# Schematic_EBook_v24.net
KiCad netlist of a schematic drawn in EAGLE
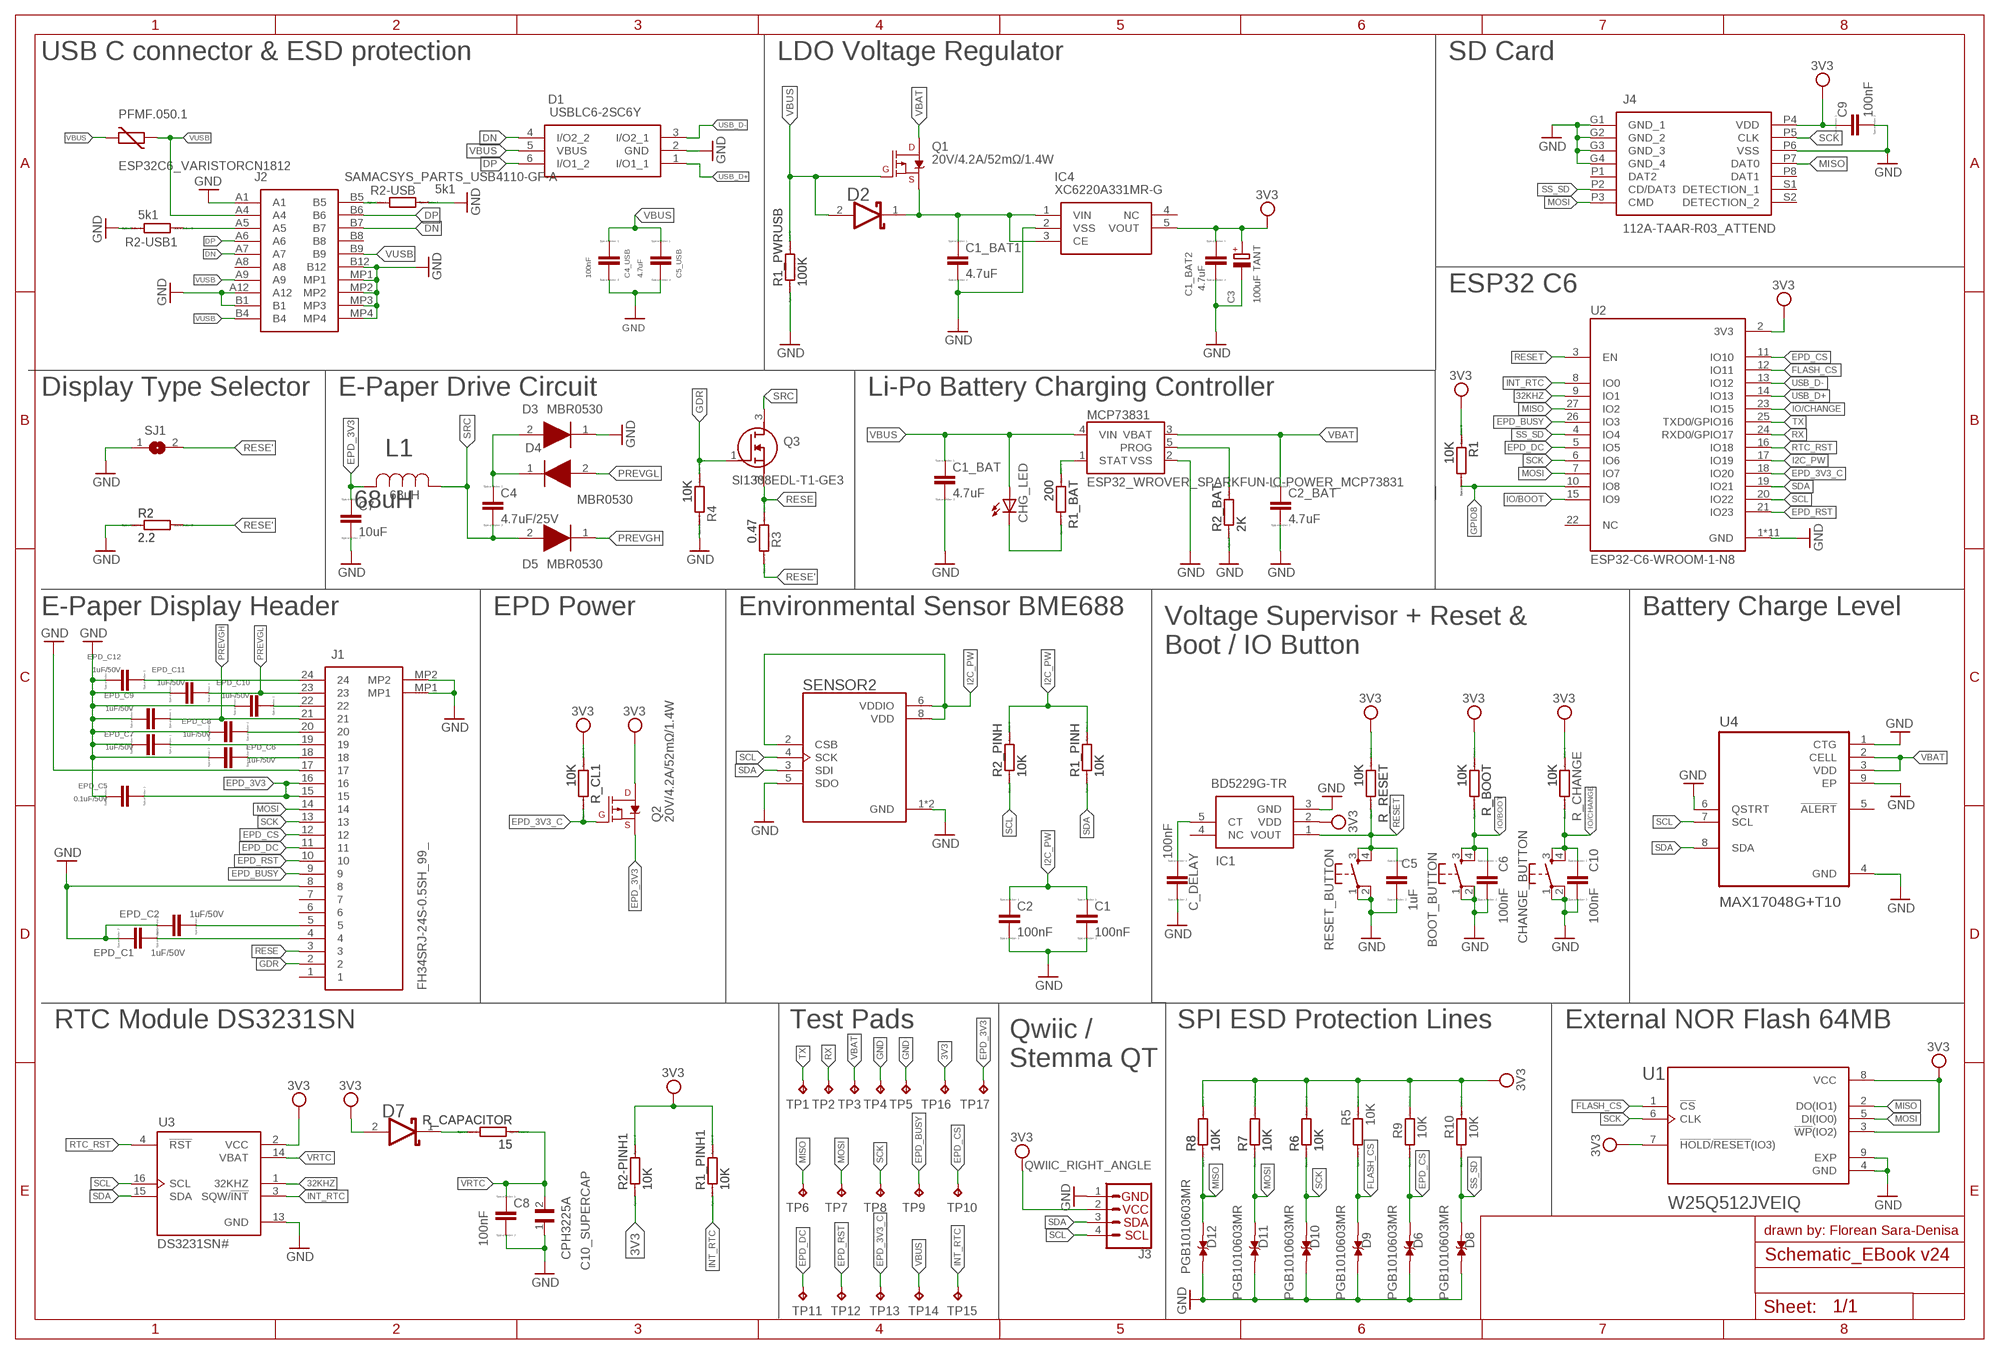
[diagram p0: schematic, sheet 1]

(export (version "E")
  (design (tool "Eeschema 10.0.6"))
  (components
    (comp (ref "BOOT_BUTTON")
      (value "BUTTON_CUSYOMV1")
      (footprint "eagle-import:MYBUTTON")
      (libsource (lib "eagle-import") (part "BUTTON_CUSYOMV1"))
    )
    (comp (ref "C1")
      (value "100nF")
      (footprint "eagle-import:EAGLE-LTSPICE_C0402")
      (libsource (lib "eagle-import") (part "EAGLE-LTSPICE_CC0402"))
    )
    (comp (ref "C1_BAT")
      (value "4.7uF")
      (footprint "eagle-import:EAGLE-LTSPICE_C0402")
      (libsource (lib "eagle-import") (part "EAGLE-LTSPICE_CC0402"))
    )
    (comp (ref "C1_BAT1")
      (value "4.7uF")
      (footprint "eagle-import:EAGLE-LTSPICE_C0402")
      (libsource (lib "eagle-import") (part "EAGLE-LTSPICE_CC0402"))
    )
    (comp (ref "C1_BAT2")
      (value "4.7uF")
      (footprint "eagle-import:EAGLE-LTSPICE_C0402")
      (libsource (lib "eagle-import") (part "ESP32_WROVER_EAGLE-LTSPICE_CC0402"))
    )
    (comp (ref "C2")
      (value "100nF")
      (footprint "eagle-import:EAGLE-LTSPICE_C0402")
      (libsource (lib "eagle-import") (part "EAGLE-LTSPICE_CC0402"))
    )
    (comp (ref "C2_BAT")
      (value "4.7uF")
      (footprint "eagle-import:EAGLE-LTSPICE_C0402")
      (libsource (lib "eagle-import") (part "EAGLE-LTSPICE_CC0402"))
    )
    (comp (ref "C3")
      (value "100uF TANT")
      (footprint "eagle-import:RCL_CT3528")
      (libsource (lib "eagle-import") (part "RCL_CPOL-EUCT3528"))
    )
    (comp (ref "C4")
      (value "4.7uF/25V")
      (footprint "eagle-import:EAGLE-LTSPICE_C0402")
      (libsource (lib "eagle-import") (part "EAGLE-LTSPICE_CC0402"))
    )
    (comp (ref "C4_USB")
      (value "100nF")
      (footprint "eagle-import:EAGLE-LTSPICE_C0402")
      (libsource (lib "eagle-import") (part "EAGLE-LTSPICE_CC0402"))
    )
    (comp (ref "C5")
      (value "1uF")
      (footprint "eagle-import:EAGLE-LTSPICE_C0402")
      (libsource (lib "eagle-import") (part "EAGLE-LTSPICE_CC0402"))
    )
    (comp (ref "C5_USB")
      (value "4.7uF")
      (footprint "eagle-import:EAGLE-LTSPICE_C0402")
      (libsource (lib "eagle-import") (part "EAGLE-LTSPICE_CC0402"))
    )
    (comp (ref "C6")
      (value "100nF")
      (footprint "eagle-import:EAGLE-LTSPICE_C0402")
      (libsource (lib "eagle-import") (part "EAGLE-LTSPICE_CC0402"))
    )
    (comp (ref "C7")
      (value "10uF")
      (footprint "eagle-import:EAGLE-LTSPICE_C0402")
      (libsource (lib "eagle-import") (part "EAGLE-LTSPICE_CC0402"))
    )
    (comp (ref "C8")
      (value "100nF")
      (footprint "eagle-import:EAGLE-LTSPICE_C0402")
      (libsource (lib "eagle-import") (part "EAGLE-LTSPICE_CC0402"))
    )
    (comp (ref "C9")
      (value "100nF")
      (footprint "eagle-import:EAGLE-LTSPICE_C0402")
      (libsource (lib "eagle-import") (part "EAGLE-LTSPICE_CC0402"))
    )
    (comp (ref "C10")
      (value "100nF")
      (footprint "eagle-import:EAGLE-LTSPICE_C0402")
      (libsource (lib "eagle-import") (part "EAGLE-LTSPICE_CC0402"))
    )
    (comp (ref "C10_SUPERCAP")
      (value "CPH3225A")
      (footprint "eagle-import:CAPCP3225X100N")
      (fields (field (name "MF") "Seiko Instruments"))
      (libsource (lib "eagle-import") (part "CPH3225A"))
    )
    (comp (ref "CHANGE_BUTTON")
      (value "BUTTON_CUSYOMV1")
      (footprint "eagle-import:MYBUTTON")
      (libsource (lib "eagle-import") (part "BUTTON_CUSYOMV1"))
    )
    (comp (ref "CHG_LED")
      (value "&")
      (footprint "eagle-import:ADAFRUIT_CHIP-LED0603")
      (libsource (lib "eagle-import") (part "ADAFRUIT_LEDCHIP-LED0603"))
    )
    (comp (ref "C_DELAY")
      (value "100nF")
      (footprint "eagle-import:EAGLE-LTSPICE_C0402")
      (libsource (lib "eagle-import") (part "EAGLE-LTSPICE_CC0402"))
    )
    (comp (ref "D1")
      (value "USBLC6-2SC6Y")
      (footprint "eagle-import:SOT95P280X145-6N")
      (fields (field (name "MF") "STMicroelectronics"))
      (libsource (lib "eagle-import") (part "USBLC6-2SC6Y"))
    )
    (comp (ref "D2")
      (value "ESP32_WROVER_AVX---SD0805S020S1R0_AVX_SD0805S020S1R0_0_0AVX_SD0805S020S1R0_0_0")
      (footprint "eagle-import:ESP32_WROVER_AVX---SD0805S020S1R0_AVX_SD0805S020S1R0_0")
      (fields
        (field (name "DIGIKEY_PART_NUMBER") "478-7800-1-ND")
        (field (name "MF") "AVX")
        (field (name "MOUSER_PART_NUMBER") "581-SD0805S020S1R0")
      )
      (libsource (lib "eagle-import") (part "ESP32_WROVER_AVX---SD0805S020S1R0_AVX_SD0805S020S1R0_0_0AVX_SD0805S020S1R0_0_0"))
    )
    (comp (ref "D3")
      (value "MBR0530")
      (footprint "eagle-import:SOD3716X135N")
      (fields (field (name "MF") "ON Semiconductor"))
      (libsource (lib "eagle-import") (part "MBR0530"))
    )
    (comp (ref "D4")
      (value "MBR0530")
      (footprint "eagle-import:SOD3716X135N")
      (fields (field (name "MF") "ON Semiconductor"))
      (libsource (lib "eagle-import") (part "MBR0530"))
    )
    (comp (ref "D5")
      (value "MBR0530")
      (footprint "eagle-import:SOD3716X135N")
      (fields (field (name "MF") "ON Semiconductor"))
      (libsource (lib "eagle-import") (part "MBR0530"))
    )
    (comp (ref "D6")
      (value "PGB1010603MR")
      (footprint "eagle-import:DIOC1608X36N")
      (fields (field (name "MF") "Littelfuse Inc."))
      (libsource (lib "eagle-import") (part "PGB1010603MR"))
    )
    (comp (ref "D7")
      (value "ESP32_WROVER_AVX---SD0805S020S1R0_AVX_SD0805S020S1R0_0_0AVX_SD0805S020S1R0_0_0")
      (footprint "eagle-import:ESP32_WROVER_AVX---SD0805S020S1R0_AVX_SD0805S020S1R0_0")
      (fields
        (field (name "DIGIKEY_PART_NUMBER") "478-7800-1-ND")
        (field (name "MF") "AVX")
        (field (name "MOUSER_PART_NUMBER") "581-SD0805S020S1R0")
      )
      (libsource (lib "eagle-import") (part "ESP32_WROVER_AVX---SD0805S020S1R0_AVX_SD0805S020S1R0_0_0AVX_SD0805S020S1R0_0_0"))
    )
    (comp (ref "D8")
      (value "PGB1010603MR")
      (footprint "eagle-import:DIOC1608X36N")
      (fields (field (name "MF") "Littelfuse Inc."))
      (libsource (lib "eagle-import") (part "PGB1010603MR"))
    )
    (comp (ref "D9")
      (value "PGB1010603MR")
      (footprint "eagle-import:DIOC1608X36N")
      (fields (field (name "MF") "Littelfuse Inc."))
      (libsource (lib "eagle-import") (part "PGB1010603MR"))
    )
    (comp (ref "D10")
      (value "PGB1010603MR")
      (footprint "eagle-import:DIOC1608X36N")
      (fields (field (name "MF") "Littelfuse Inc."))
      (libsource (lib "eagle-import") (part "PGB1010603MR"))
    )
    (comp (ref "D11")
      (value "PGB1010603MR")
      (footprint "eagle-import:DIOC1608X36N")
      (fields (field (name "MF") "Littelfuse Inc."))
      (libsource (lib "eagle-import") (part "PGB1010603MR"))
    )
    (comp (ref "D12")
      (value "PGB1010603MR")
      (footprint "eagle-import:DIOC1608X36N")
      (fields (field (name "MF") "Littelfuse Inc."))
      (libsource (lib "eagle-import") (part "PGB1010603MR"))
    )
    (comp (ref "EPD_C1")
      (value "1uF/50V")
      (footprint "eagle-import:EAGLE-LTSPICE_C0402")
      (libsource (lib "eagle-import") (part "EAGLE-LTSPICE_CC0402"))
    )
    (comp (ref "EPD_C2")
      (value "1uF/50V")
      (footprint "eagle-import:EAGLE-LTSPICE_C0402")
      (libsource (lib "eagle-import") (part "EAGLE-LTSPICE_CC0402"))
    )
    (comp (ref "EPD_C5")
      (value "0.1uF/50V")
      (footprint "eagle-import:EAGLE-LTSPICE_C0402")
      (libsource (lib "eagle-import") (part "EAGLE-LTSPICE_CC0402"))
    )
    (comp (ref "EPD_C6")
      (value "1uF/50V")
      (footprint "eagle-import:EAGLE-LTSPICE_C0402")
      (libsource (lib "eagle-import") (part "EAGLE-LTSPICE_CC0402"))
    )
    (comp (ref "EPD_C7")
      (value "1uF/50V")
      (footprint "eagle-import:EAGLE-LTSPICE_C0402")
      (libsource (lib "eagle-import") (part "EAGLE-LTSPICE_CC0402"))
    )
    (comp (ref "EPD_C8")
      (value "1uF/50V")
      (footprint "eagle-import:EAGLE-LTSPICE_C0402")
      (libsource (lib "eagle-import") (part "EAGLE-LTSPICE_CC0402"))
    )
    (comp (ref "EPD_C9")
      (value "1uF/50V")
      (footprint "eagle-import:EAGLE-LTSPICE_C0402")
      (libsource (lib "eagle-import") (part "EAGLE-LTSPICE_CC0402"))
    )
    (comp (ref "EPD_C10")
      (value "1uF/50V")
      (footprint "eagle-import:EAGLE-LTSPICE_C0402")
      (libsource (lib "eagle-import") (part "EAGLE-LTSPICE_CC0402"))
    )
    (comp (ref "EPD_C11")
      (value "1uF/50V")
      (footprint "eagle-import:EAGLE-LTSPICE_C0402")
      (libsource (lib "eagle-import") (part "EAGLE-LTSPICE_CC0402"))
    )
    (comp (ref "EPD_C12")
      (value "1uF/50V")
      (footprint "eagle-import:EAGLE-LTSPICE_C0402")
      (libsource (lib "eagle-import") (part "EAGLE-LTSPICE_CC0402"))
    )
    (comp (ref "IC1")
      (value "BD5229G-TR")
      (footprint "eagle-import:SOT95P280X125-5N")
      (fields (field (name "MOUSER_PART_NUMBER") "755-BD5229G-TR"))
      (libsource (lib "eagle-import") (part "BD5229G-TR"))
    )
    (comp (ref "IC4")
      (value "XC6220A331MR-G")
      (footprint "eagle-import:SOT95P280X120-5N")
      (fields (field (name "MOUSER_PART_NUMBER") "865-XC6220A331MR-G"))
      (libsource (lib "eagle-import") (part "XC6220A331MR-G"))
    )
    (comp (ref "J1")
      (value "FH34SRJ-24S-0.5SH_99_")
      (footprint "eagle-import:FH34SRJ24S05SH99")
      (fields
        (field (name "MANUFACTURER_PART_NUMBER") "FH34SRJ-24S-0.5SH(99)")
        (field (name "MOUSER_PART_NUMBER") "798-FH34SRJ24S05SH99")
      )
      (libsource (lib "eagle-import") (part "FH34SRJ-24S-0.5SH_99_"))
    )
    (comp (ref "J2")
      (value "SAMACSYS_PARTS_USB4110-GF-A")
      (footprint "eagle-import:SAMACSYS_PARTS_USB4110GFA")
      (fields
        (field (name "MANUFACTURER_PART_NUMBER") "USB4110-GF-A")
        (field (name "MOUSER_PART_NUMBER") "640-USB4110-GF-A")
      )
      (libsource (lib "eagle-import") (part "SAMACSYS_PARTS_USB4110-GF-A"))
    )
    (comp (ref "J3")
      (value "QWIIC_RIGHT_ANGLE")
      (footprint "eagle-import:JST04_1MM_RA")
      (libsource (lib "eagle-import") (part "QWIIC_CONNECTORJS-1MM"))
    )
    (comp (ref "J4")
      (value "112A-TAAR-R03_ATTEND")
      (footprint "eagle-import:112ATAARR03ATTEND")
      (fields (field (name "MANUFACTURER_PART_NUMBER") "112A-TAAR-R03 ATTEND"))
      (libsource (lib "eagle-import") (part "112A-TAAR-R03_ATTEND"))
    )
    (comp (ref "L1")
      (value "68uH")
      (footprint "eagle-import:IND_4828-WE-TPC_WRE")
      (fields
        (field (name "MANUFACTURER_PART_NUMBER") "744043680")
        (field (name "COPYRIGHT") "Copyright (C) 2024 Ultra Librarian. All rights reserved.")
      )
      (libsource (lib "eagle-import") (part "744043680IND_4828-WE-TPC_WRE"))
    )
    (comp (ref "MCP73831")
      (value "ESP32_WROVER_SPARKFUN-IC-POWER_MCP73831")
      (footprint "eagle-import:ESP32_WROVER_SPARKFUN-IC-POWER_SOT23-5")
      (libsource (lib "eagle-import") (part "ESP32_WROVER_SPARKFUN-IC-POWER_MCP73831"))
    )
    (comp (ref "PFMF.050.1")
      (value "ESP32C6_VARISTORCN1812")
      (footprint "eagle-import:ESP32C6_VARISTOR_CT_CN1812")
      (libsource (lib "eagle-import") (part "ESP32C6_VARISTORCN1812"))
    )
    (comp (ref "Q1")
      (value "20V/4.2A/52mΩ/1.4W")
      (footprint "eagle-import:ESP32_WROVER_SPARKFUN-DISCRETESEMI_SOT23-3")
      (libsource (lib "eagle-import") (part "ESP32_WROVER_SPARKFUN-DISCRETESEMI_MOSFET_PCH-DMG2305UX-7"))
    )
    (comp (ref "Q2")
      (value "20V/4.2A/52mΩ/1.4W")
      (footprint "eagle-import:ESP32_WROVER_SPARKFUN-DISCRETESEMI_SOT23-3")
      (libsource (lib "eagle-import") (part "ESP32_WROVER_SPARKFUN-DISCRETESEMI_MOSFET_PCH-DMG2305UX-7"))
    )
    (comp (ref "Q3")
      (value "SI1308EDL-T1-GE3")
      (footprint "eagle-import:SOT65P210X110-3N")
      (fields (field (name "MF") "Vishay Siliconix"))
      (libsource (lib "eagle-import") (part "SI1308EDL-T1-GE3"))
    )
    (comp (ref "R1")
      (value "10K")
      (footprint "eagle-import:ESP32_WROVER_EAGLE-LTSPICE_R0402")
      (libsource (lib "eagle-import") (part "ESP32_WROVER_EAGLE-LTSPICE_RR0402"))
    )
    (comp (ref "R1_BAT")
      (value "200")
      (footprint "eagle-import:ESP32_WROVER_EAGLE-LTSPICE_R0402")
      (libsource (lib "eagle-import") (part "ESP32_WROVER_EAGLE-LTSPICE_RR0402"))
    )
    (comp (ref "R1_PINH")
      (value "10K")
      (footprint "eagle-import:ESP32_WROVER_EAGLE-LTSPICE_R0402")
      (libsource (lib "eagle-import") (part "ESP32_WROVER_EAGLE-LTSPICE_RR0402"))
    )
    (comp (ref "R1_PINH1")
      (value "10K")
      (footprint "eagle-import:ESP32_WROVER_EAGLE-LTSPICE_R0402")
      (libsource (lib "eagle-import") (part "ESP32_WROVER_EAGLE-LTSPICE_RR0402"))
    )
    (comp (ref "R1_PWRUSB")
      (value "100K")
      (footprint "eagle-import:ESP32_WROVER_EAGLE-LTSPICE_R0402")
      (libsource (lib "eagle-import") (part "ESP32_WROVER_EAGLE-LTSPICE_RR0402"))
    )
    (comp (ref "R2")
      (value "2.2")
      (footprint "eagle-import:ESP32_WROVER_EAGLE-LTSPICE_R0402")
      (libsource (lib "eagle-import") (part "ESP32_WROVER_EAGLE-LTSPICE_RR0402"))
    )
    (comp (ref "R2-PINH1")
      (value "10K")
      (footprint "eagle-import:ESP32_WROVER_EAGLE-LTSPICE_R0402")
      (libsource (lib "eagle-import") (part "ESP32_WROVER_EAGLE-LTSPICE_RR0402"))
    )
    (comp (ref "R2-USB")
      (value "5k1")
      (footprint "eagle-import:ESP32_WROVER_EAGLE-LTSPICE_R0402")
      (libsource (lib "eagle-import") (part "ESP32_WROVER_EAGLE-LTSPICE_RR0402"))
    )
    (comp (ref "R2-USB1")
      (value "5k1")
      (footprint "eagle-import:ESP32_WROVER_EAGLE-LTSPICE_R0402")
      (libsource (lib "eagle-import") (part "ESP32_WROVER_EAGLE-LTSPICE_RR0402"))
    )
    (comp (ref "R2_BAT")
      (value "2K")
      (footprint "eagle-import:ESP32_WROVER_EAGLE-LTSPICE_R0402")
      (libsource (lib "eagle-import") (part "ESP32_WROVER_EAGLE-LTSPICE_RR0402"))
    )
    (comp (ref "R2_PINH")
      (value "10K")
      (footprint "eagle-import:ESP32_WROVER_EAGLE-LTSPICE_R0402")
      (libsource (lib "eagle-import") (part "ESP32_WROVER_EAGLE-LTSPICE_RR0402"))
    )
    (comp (ref "R3")
      (value "0.47")
      (footprint "eagle-import:ESP32_WROVER_EAGLE-LTSPICE_R0402")
      (libsource (lib "eagle-import") (part "ESP32_WROVER_EAGLE-LTSPICE_RR0402"))
    )
    (comp (ref "R4")
      (value "10K")
      (footprint "eagle-import:ESP32_WROVER_EAGLE-LTSPICE_R0402")
      (libsource (lib "eagle-import") (part "ESP32_WROVER_EAGLE-LTSPICE_RR0402"))
    )
    (comp (ref "R5")
      (value "10K")
      (footprint "eagle-import:ESP32_WROVER_EAGLE-LTSPICE_R0402")
      (libsource (lib "eagle-import") (part "ESP32_WROVER_EAGLE-LTSPICE_RR0402"))
    )
    (comp (ref "R6")
      (value "10K")
      (footprint "eagle-import:ESP32_WROVER_EAGLE-LTSPICE_R0402")
      (libsource (lib "eagle-import") (part "ESP32_WROVER_EAGLE-LTSPICE_RR0402"))
    )
    (comp (ref "R7")
      (value "10K")
      (footprint "eagle-import:ESP32_WROVER_EAGLE-LTSPICE_R0402")
      (libsource (lib "eagle-import") (part "ESP32_WROVER_EAGLE-LTSPICE_RR0402"))
    )
    (comp (ref "R8")
      (value "10K")
      (footprint "eagle-import:ESP32_WROVER_EAGLE-LTSPICE_R0402")
      (libsource (lib "eagle-import") (part "ESP32_WROVER_EAGLE-LTSPICE_RR0402"))
    )
    (comp (ref "R9")
      (value "10K")
      (footprint "eagle-import:ESP32_WROVER_EAGLE-LTSPICE_R0402")
      (libsource (lib "eagle-import") (part "ESP32_WROVER_EAGLE-LTSPICE_RR0402"))
    )
    (comp (ref "R10")
      (value "10K")
      (footprint "eagle-import:ESP32_WROVER_EAGLE-LTSPICE_R0402")
      (libsource (lib "eagle-import") (part "ESP32_WROVER_EAGLE-LTSPICE_RR0402"))
    )
    (comp (ref "RESET_BUTTON")
      (value "BUTTON_CUSYOMV1")
      (footprint "eagle-import:MYBUTTON")
      (libsource (lib "eagle-import") (part "BUTTON_CUSYOMV1"))
    )
    (comp (ref "R_BOOT")
      (value "10K")
      (footprint "eagle-import:ESP32_WROVER_EAGLE-LTSPICE_R0402")
      (libsource (lib "eagle-import") (part "ESP32_WROVER_EAGLE-LTSPICE_RR0402"))
    )
    (comp (ref "R_CAPACITOR")
      (value "15")
      (footprint "eagle-import:ESP32_WROVER_EAGLE-LTSPICE_R0402")
      (libsource (lib "eagle-import") (part "ESP32_WROVER_EAGLE-LTSPICE_RR0402"))
    )
    (comp (ref "R_CHANGE")
      (value "10K")
      (footprint "eagle-import:ESP32_WROVER_EAGLE-LTSPICE_R0402")
      (libsource (lib "eagle-import") (part "ESP32_WROVER_EAGLE-LTSPICE_RR0402"))
    )
    (comp (ref "R_CL1")
      (value "10K")
      (footprint "eagle-import:ESP32_WROVER_EAGLE-LTSPICE_R0402")
      (libsource (lib "eagle-import") (part "ESP32_WROVER_EAGLE-LTSPICE_RR0402"))
    )
    (comp (ref "R_RESET")
      (value "10K")
      (footprint "eagle-import:ESP32_WROVER_EAGLE-LTSPICE_R0402")
      (libsource (lib "eagle-import") (part "ESP32_WROVER_EAGLE-LTSPICE_RR0402"))
    )
    (comp (ref "SENSOR2")
      (value "ESP32_WROVER_BME680_BME680")
      (footprint "eagle-import:ESP32_WROVER_BME680_PSON80P300X300X100-8N")
      (fields (field (name "MF") "Bosch Sensortec") (field (name "MP") "BME680"))
      (libsource (lib "eagle-import") (part "ESP32_WROVER_BME680_BME680"))
    )
    (comp (ref "SJ1") (value "&") (footprint "eagle-import:SJ") (libsource (lib "eagle-import") (part "SJ")))
    (comp (ref "TP1")
      (value "TPTP20R")
      (footprint "eagle-import:TP20R")
      (libsource (lib "eagle-import") (part "TPTP20R"))
    )
    (comp (ref "TP2")
      (value "TPTP20R")
      (footprint "eagle-import:TP20R")
      (libsource (lib "eagle-import") (part "TPTP20R"))
    )
    (comp (ref "TP3")
      (value "TPTP20R")
      (footprint "eagle-import:TP20R")
      (libsource (lib "eagle-import") (part "TPTP20R"))
    )
    (comp (ref "TP4")
      (value "TPTP20R")
      (footprint "eagle-import:TP20R")
      (libsource (lib "eagle-import") (part "TPTP20R"))
    )
    (comp (ref "TP5")
      (value "TPTP20R")
      (footprint "eagle-import:TP20R")
      (libsource (lib "eagle-import") (part "TPTP20R"))
    )
    (comp (ref "TP6")
      (value "TPTP20R")
      (footprint "eagle-import:TP20R")
      (libsource (lib "eagle-import") (part "TPTP20R"))
    )
    (comp (ref "TP7")
      (value "TPTP20R")
      (footprint "eagle-import:TP20R")
      (libsource (lib "eagle-import") (part "TPTP20R"))
    )
    (comp (ref "TP8")
      (value "TPTP20R")
      (footprint "eagle-import:TP20R")
      (libsource (lib "eagle-import") (part "TPTP20R"))
    )
    (comp (ref "TP9")
      (value "TPTP20R")
      (footprint "eagle-import:TP20R")
      (libsource (lib "eagle-import") (part "TPTP20R"))
    )
    (comp (ref "TP10")
      (value "TPTP20R")
      (footprint "eagle-import:TP20R")
      (libsource (lib "eagle-import") (part "TPTP20R"))
    )
    (comp (ref "TP11")
      (value "TPTP20R")
      (footprint "eagle-import:TP20R")
      (libsource (lib "eagle-import") (part "TPTP20R"))
    )
    (comp (ref "TP12")
      (value "TPTP20R")
      (footprint "eagle-import:TP20R")
      (libsource (lib "eagle-import") (part "TPTP20R"))
    )
    (comp (ref "TP13")
      (value "TPTP20R")
      (footprint "eagle-import:TP20R")
      (libsource (lib "eagle-import") (part "TPTP20R"))
    )
    (comp (ref "TP14")
      (value "TPTP20R")
      (footprint "eagle-import:TP20R")
      (libsource (lib "eagle-import") (part "TPTP20R"))
    )
    (comp (ref "TP15")
      (value "TPTP20R")
      (footprint "eagle-import:TP20R")
      (libsource (lib "eagle-import") (part "TPTP20R"))
    )
    (comp (ref "TP16")
      (value "TPTP20R")
      (footprint "eagle-import:TP20R")
      (libsource (lib "eagle-import") (part "TPTP20R"))
    )
    (comp (ref "TP17")
      (value "TPTP20R")
      (footprint "eagle-import:TP20R")
      (libsource (lib "eagle-import") (part "TPTP20R"))
    )
    (comp (ref "U1")
      (value "W25Q512JVEIQ")
      (footprint "eagle-import:SON127P600X800X80-9N")
      (fields (field (name "MF") "Winbond Electronics"))
      (libsource (lib "eagle-import") (part "W25Q512JVEIQ"))
    )
    (comp (ref "U2")
      (value "ESP32-C6-WROOM-1-N8")
      (footprint "eagle-import:XCVR_ESP32-C6-WROOM-1-N8")
      (fields (field (name "MF") "Espressif Systems"))
      (libsource (lib "eagle-import") (part "ESP32-C6-WROOM-1-N8"))
    )
    (comp (ref "U3")
      (value "DS3231SN#")
      (footprint "eagle-import:SOIC127P1032X265-16N")
      (fields (field (name "MF") "Analog Devices"))
      (libsource (lib "eagle-import") (part "DS3231SN#"))
    )
    (comp (ref "U4")
      (value "MAX17048G+T10")
      (footprint "eagle-import:SON50P200X200X80-9N")
      (fields (field (name "MF") "Analog Devices"))
      (libsource (lib "eagle-import") (part "MAX17048G+T10"))
    )
  )
  (nets
    (net (code "1") (name "3V3") (class "Default")
      (node (ref "C1_BAT2") (pin "1") (pinfunction "1_1") (pintype "passive"))
      (node (ref "C3") (pin "+") (pinfunction "+_+") (pintype "passive"))
      (node (ref "C9") (pin "1") (pinfunction "1_1") (pintype "passive"))
      (node (ref "D7") (pin "2") (pinfunction "ANODE_2") (pintype "bidirectional"))
      (node (ref "IC1") (pin "2") (pinfunction "VDD_2") (pintype "bidirectional"))
      (node (ref "IC4") (pin "5") (pinfunction "VOUT_5") (pintype "bidirectional"))
      (node (ref "J3") (pin "2") (pinfunction "2_2") (pintype "power_in"))
      (node (ref "J4") (pin "P4") (pinfunction "VDD_P4") (pintype "bidirectional"))
      (node (ref "Q2") (pin "3") (pinfunction "D_3") (pintype "bidirectional"))
      (node (ref "R1") (pin "1") (pinfunction "1_1") (pintype "passive"))
      (node (ref "R10") (pin "2") (pinfunction "2_2") (pintype "passive"))
      (node (ref "R1_PINH1") (pin "2") (pinfunction "2_2") (pintype "passive"))
      (node (ref "R2-PINH1") (pin "1") (pinfunction "1_1") (pintype "passive"))
      (node (ref "R2-PINH1") (pin "2") (pinfunction "2_2") (pintype "passive"))
      (node (ref "R5") (pin "2") (pinfunction "2_2") (pintype "passive"))
      (node (ref "R6") (pin "2") (pinfunction "2_2") (pintype "passive"))
      (node (ref "R7") (pin "2") (pinfunction "2_2") (pintype "passive"))
      (node (ref "R8") (pin "2") (pinfunction "2_2") (pintype "passive"))
      (node (ref "R9") (pin "2") (pinfunction "2_2") (pintype "passive"))
      (node (ref "R_BOOT") (pin "1") (pinfunction "1_1") (pintype "passive"))
      (node (ref "R_CHANGE") (pin "1") (pinfunction "1_1") (pintype "passive"))
      (node (ref "R_CL1") (pin "1") (pinfunction "1_1") (pintype "passive"))
      (node (ref "R_RESET") (pin "1") (pinfunction "1_1") (pintype "passive"))
      (node (ref "TP16") (pin "TP") (pinfunction "TP_TP") (pintype "input"))
      (node (ref "U1") (pin "3") (pinfunction "~{WP}(IO2)_3") (pintype "bidirectional"))
      (node (ref "U1") (pin "7") (pinfunction "~{HOLD}/~{RESET}(IO3)_7") (pintype "bidirectional"))
      (node (ref "U1") (pin "8") (pinfunction "VCC_8") (pintype "power_in"))
      (node (ref "U2") (pin "2") (pinfunction "3V3_2") (pintype "power_in"))
      (node (ref "U3") (pin "2") (pinfunction "VCC_2") (pintype "power_in"))
    )
    (net (code "2") (name "32KHZ") (class "Default")
      (node (ref "U2") (pin "9") (pinfunction "IO1_9") (pintype "bidirectional"))
      (node (ref "U3") (pin "1") (pinfunction "32KHZ_1") (pintype "output"))
    )
    (net (code "3") (name "DN") (class "Default")
      (node (ref "D1") (pin "4") (pinfunction "I/O2_2_4") (pintype "bidirectional"))
      (node (ref "J2") (pin "A7") (pinfunction "A7_A7") (pintype "bidirectional"))
      (node (ref "J2") (pin "B7") (pinfunction "B7_B7") (pintype "bidirectional"))
    )
    (net (code "4") (name "DP") (class "Default")
      (node (ref "D1") (pin "6") (pinfunction "I/O1_2_6") (pintype "bidirectional"))
      (node (ref "J2") (pin "A6") (pinfunction "A6_A6") (pintype "bidirectional"))
      (node (ref "J2") (pin "B6") (pinfunction "B6_B6") (pintype "bidirectional"))
    )
    (net (code "5") (name "EPD_3V3") (class "Default")
      (node (ref "C7") (pin "1") (pinfunction "1_1") (pintype "passive"))
      (node (ref "EPD_C5") (pin "1") (pinfunction "1_1") (pintype "passive"))
      (node (ref "J1") (pin "15") (pinfunction "15_15") (pintype "bidirectional"))
      (node (ref "J1") (pin "16") (pinfunction "16_16") (pintype "bidirectional"))
      (node (ref "L1") (pin "2") (pinfunction "2_2") (pintype "passive"))
      (node (ref "Q2") (pin "2") (pinfunction "S_2") (pintype "bidirectional"))
      (node (ref "TP17") (pin "TP") (pinfunction "TP_TP") (pintype "input"))
    )
    (net (code "6") (name "EPD_3V3_C") (class "Default")
      (node (ref "Q2") (pin "1") (pinfunction "G_1") (pintype "bidirectional"))
      (node (ref "R_CL1") (pin "2") (pinfunction "2_2") (pintype "passive"))
      (node (ref "TP13") (pin "TP") (pinfunction "TP_TP") (pintype "input"))
      (node (ref "U2") (pin "18") (pinfunction "IO20_18") (pintype "bidirectional"))
    )
    (net (code "7") (name "EPD_BUSY") (class "Default")
      (node (ref "J1") (pin "9") (pinfunction "9_9") (pintype "bidirectional"))
      (node (ref "TP9") (pin "TP") (pinfunction "TP_TP") (pintype "input"))
      (node (ref "U2") (pin "26") (pinfunction "IO3_26") (pintype "bidirectional"))
    )
    (net (code "8") (name "EPD_CS") (class "Default")
      (node (ref "D6") (pin "2") (pinfunction "2_2") (pintype "passive"))
      (node (ref "J1") (pin "12") (pinfunction "12_12") (pintype "bidirectional"))
      (node (ref "R9") (pin "1") (pinfunction "1_1") (pintype "passive"))
      (node (ref "TP10") (pin "TP") (pinfunction "TP_TP") (pintype "input"))
      (node (ref "U2") (pin "11") (pinfunction "IO10_11") (pintype "bidirectional"))
    )
    (net (code "9") (name "EPD_DC") (class "Default")
      (node (ref "J1") (pin "11") (pinfunction "11_11") (pintype "bidirectional"))
      (node (ref "TP11") (pin "TP") (pinfunction "TP_TP") (pintype "input"))
      (node (ref "U2") (pin "5") (pinfunction "IO5_5") (pintype "bidirectional"))
    )
    (net (code "10") (name "EPD_RST") (class "Default")
      (node (ref "J1") (pin "10") (pinfunction "10_10") (pintype "bidirectional"))
      (node (ref "TP12") (pin "TP") (pinfunction "TP_TP") (pintype "input"))
      (node (ref "U2") (pin "21") (pinfunction "IO23_21") (pintype "bidirectional"))
    )
    (net (code "11") (name "FLASH_CS") (class "Default")
      (node (ref "D9") (pin "2") (pinfunction "2_2") (pintype "passive"))
      (node (ref "R5") (pin "1") (pinfunction "1_1") (pintype "passive"))
      (node (ref "U1") (pin "1") (pinfunction "~{CS}_1") (pintype "input"))
      (node (ref "U2") (pin "12") (pinfunction "IO11_12") (pintype "bidirectional"))
    )
    (net (code "12") (name "GDR") (class "Default")
      (node (ref "J1") (pin "2") (pinfunction "2_2") (pintype "bidirectional"))
      (node (ref "Q3") (pin "1") (pinfunction "G_1") (pintype "bidirectional"))
      (node (ref "R4") (pin "1") (pinfunction "1_1") (pintype "passive"))
    )
    (net (code "13") (name "GND") (class "Default")
      (node (ref "BOOT_BUTTON") (pin "1") (pinfunction "1_1") (pintype "passive"))
      (node (ref "BOOT_BUTTON") (pin "2") (pinfunction "2_2") (pintype "passive"))
      (node (ref "C1") (pin "2") (pinfunction "2_2") (pintype "passive"))
      (node (ref "C10") (pin "2") (pinfunction "2_2") (pintype "passive"))
      (node (ref "C10_SUPERCAP") (pin "1") (pinfunction "1_1") (pintype "passive"))
      (node (ref "C1_BAT") (pin "2") (pinfunction "2_2") (pintype "passive"))
      (node (ref "C1_BAT1") (pin "2") (pinfunction "2_2") (pintype "passive"))
      (node (ref "C1_BAT2") (pin "2") (pinfunction "2_2") (pintype "passive"))
      (node (ref "C2") (pin "2") (pinfunction "2_2") (pintype "passive"))
      (node (ref "C2_BAT") (pin "2") (pinfunction "2_2") (pintype "passive"))
      (node (ref "C3") (pin "-") (pinfunction "-_-") (pintype "passive"))
      (node (ref "C4_USB") (pin "2") (pinfunction "2_2") (pintype "passive"))
      (node (ref "C5") (pin "2") (pinfunction "2_2") (pintype "passive"))
      (node (ref "C5_USB") (pin "2") (pinfunction "2_2") (pintype "passive"))
      (node (ref "C6") (pin "2") (pinfunction "2_2") (pintype "passive"))
      (node (ref "C7") (pin "2") (pinfunction "2_2") (pintype "passive"))
      (node (ref "C8") (pin "2") (pinfunction "2_2") (pintype "passive"))
      (node (ref "C9") (pin "2") (pinfunction "2_2") (pintype "passive"))
      (node (ref "CHANGE_BUTTON") (pin "1") (pinfunction "1_1") (pintype "passive"))
      (node (ref "CHANGE_BUTTON") (pin "2") (pinfunction "2_2") (pintype "passive"))
      (node (ref "C_DELAY") (pin "2") (pinfunction "2_2") (pintype "passive"))
      (node (ref "D1") (pin "2") (pinfunction "GND_2") (pintype "bidirectional"))
      (node (ref "D10") (pin "1") (pinfunction "1_1") (pintype "passive"))
      (node (ref "D11") (pin "1") (pinfunction "1_1") (pintype "passive"))
      (node (ref "D12") (pin "1") (pinfunction "1_1") (pintype "passive"))
      (node (ref "D3") (pin "1") (pinfunction "K_1") (pintype "bidirectional"))
      (node (ref "D6") (pin "1") (pinfunction "1_1") (pintype "passive"))
      (node (ref "D8") (pin "1") (pinfunction "1_1") (pintype "passive"))
      (node (ref "D9") (pin "1") (pinfunction "1_1") (pintype "passive"))
      (node (ref "EPD_C1") (pin "2") (pinfunction "2_2") (pintype "passive"))
      (node (ref "EPD_C10") (pin "2") (pinfunction "2_2") (pintype "passive"))
      (node (ref "EPD_C11") (pin "2") (pinfunction "2_2") (pintype "passive"))
      (node (ref "EPD_C12") (pin "2") (pinfunction "2_2") (pintype "passive"))
      (node (ref "EPD_C2") (pin "2") (pinfunction "2_2") (pintype "passive"))
      (node (ref "EPD_C5") (pin "2") (pinfunction "2_2") (pintype "passive"))
      (node (ref "EPD_C6") (pin "2") (pinfunction "2_2") (pintype "passive"))
      (node (ref "EPD_C7") (pin "2") (pinfunction "2_2") (pintype "passive"))
      (node (ref "EPD_C8") (pin "2") (pinfunction "2_2") (pintype "passive"))
      (node (ref "EPD_C9") (pin "2") (pinfunction "2_2") (pintype "passive"))
      (node (ref "IC1") (pin "3") (pinfunction "GND_3") (pintype "bidirectional"))
      (node (ref "IC4") (pin "2") (pinfunction "VSS_2") (pintype "bidirectional"))
      (node (ref "J1") (pin "17") (pinfunction "17_17") (pintype "bidirectional"))
      (node (ref "J1") (pin "8") (pinfunction "8_8") (pintype "bidirectional"))
      (node (ref "J1") (pin "MP1") (pinfunction "MP1_MP1") (pintype "bidirectional"))
      (node (ref "J1") (pin "MP2") (pinfunction "MP2_MP2") (pintype "bidirectional"))
      (node (ref "J2") (pin "A1") (pinfunction "A1_A1") (pintype "bidirectional"))
      (node (ref "J2") (pin "A12") (pinfunction "A12_A12") (pintype "bidirectional"))
      (node (ref "J2") (pin "B1") (pinfunction "B1_B1") (pintype "bidirectional"))
      (node (ref "J2") (pin "B12") (pinfunction "B12_B12") (pintype "bidirectional"))
      (node (ref "J2") (pin "MP1") (pinfunction "MP1_MP1") (pintype "bidirectional"))
      (node (ref "J2") (pin "MP2") (pinfunction "MP2_MP2") (pintype "bidirectional"))
      (node (ref "J2") (pin "MP3") (pinfunction "MP3_MP3") (pintype "bidirectional"))
      (node (ref "J2") (pin "MP4") (pinfunction "MP4_MP4") (pintype "bidirectional"))
      (node (ref "J3") (pin "1") (pinfunction "1_1") (pintype "power_in"))
      (node (ref "J4") (pin "G1") (pinfunction "GND_1_G1") (pintype "bidirectional"))
      (node (ref "J4") (pin "G2") (pinfunction "GND_2_G2") (pintype "bidirectional"))
      (node (ref "J4") (pin "G3") (pinfunction "GND_3_G3") (pintype "bidirectional"))
      (node (ref "J4") (pin "G4") (pinfunction "GND_4_G4") (pintype "bidirectional"))
      (node (ref "J4") (pin "P6") (pinfunction "VSS_P6") (pintype "bidirectional"))
      (node (ref "MCP73831") (pin "2") (pinfunction "VSS_2") (pintype "power_in"))
      (node (ref "R1_PWRUSB") (pin "1") (pinfunction "1_1") (pintype "passive"))
      (node (ref "R2") (pin "1") (pinfunction "1_1") (pintype "passive"))
      (node (ref "R2-USB") (pin "2") (pinfunction "2_2") (pintype "passive"))
      (node (ref "R2-USB1") (pin "1") (pinfunction "1_1") (pintype "passive"))
      (node (ref "R2_BAT") (pin "1") (pinfunction "1_1") (pintype "passive"))
      (node (ref "R4") (pin "2") (pinfunction "2_2") (pintype "passive"))
      (node (ref "RESET_BUTTON") (pin "1") (pinfunction "1_1") (pintype "passive"))
      (node (ref "RESET_BUTTON") (pin "2") (pinfunction "2_2") (pintype "passive"))
      (node (ref "SENSOR2") (pin "1") (pinfunction "GND_1") (pintype "power_in"))
      (node (ref "SENSOR2") (pin "5") (pinfunction "SDO_5") (pintype "bidirectional"))
      (node (ref "SENSOR2") (pin "7") (pinfunction "GND_7") (pintype "power_in"))
      (node (ref "SJ1") (pin "1") (pinfunction "1_1") (pintype "passive"))
      (node (ref "TP4") (pin "TP") (pinfunction "TP_TP") (pintype "input"))
      (node (ref "TP5") (pin "TP") (pinfunction "TP_TP") (pintype "input"))
      (node (ref "U1") (pin "4") (pinfunction "GND_4") (pintype "power_in"))
      (node (ref "U1") (pin "9") (pinfunction "EXP_9") (pintype "passive"))
      (node (ref "U2") (pin "1") (pinfunction "GND_1") (pintype "power_in"))
      (node (ref "U2") (pin "28") (pinfunction "GND_28") (pintype "power_in"))
      (node (ref "U2") (pin "29_1") (pinfunction "GND_29_1") (pintype "power_in"))
      (node (ref "U2") (pin "29_2") (pinfunction "GND_29_2") (pintype "power_in"))
      (node (ref "U2") (pin "29_3") (pinfunction "GND_29_3") (pintype "power_in"))
      (node (ref "U2") (pin "29_4") (pinfunction "GND_29_4") (pintype "power_in"))
      (node (ref "U2") (pin "29_5") (pinfunction "GND_29_5") (pintype "power_in"))
      (node (ref "U2") (pin "29_6") (pinfunction "GND_29_6") (pintype "power_in"))
      (node (ref "U2") (pin "29_7") (pinfunction "GND_29_7") (pintype "power_in"))
      (node (ref "U2") (pin "29_8") (pinfunction "GND_29_8") (pintype "power_in"))
      (node (ref "U2") (pin "29_9") (pinfunction "GND_29_9") (pintype "power_in"))
      (node (ref "U3") (pin "13") (pinfunction "GND_13") (pintype "power_in"))
      (node (ref "U4") (pin "1") (pinfunction "CTG_1") (pintype "power_in"))
      (node (ref "U4") (pin "4") (pinfunction "GND_4") (pintype "power_in"))
      (node (ref "U4") (pin "6") (pinfunction "QSTRT_6") (pintype "input"))
      (node (ref "U4") (pin "9") (pinfunction "EP_9") (pintype "power_in"))
    )
    (net (code "14") (name "GPIO8") (class "Default")
      (node (ref "R1") (pin "2") (pinfunction "2_2") (pintype "passive"))
      (node (ref "U2") (pin "10") (pinfunction "IO8_10") (pintype "bidirectional"))
    )
    (net (code "15") (name "I2C_PW") (class "Default")
      (node (ref "C1") (pin "1") (pinfunction "1_1") (pintype "passive"))
      (node (ref "C2") (pin "1") (pinfunction "1_1") (pintype "passive"))
      (node (ref "R1_PINH") (pin "2") (pinfunction "2_2") (pintype "passive"))
      (node (ref "R2_PINH") (pin "2") (pinfunction "2_2") (pintype "passive"))
      (node (ref "SENSOR2") (pin "2") (pinfunction "CSB_2") (pintype "input"))
      (node (ref "SENSOR2") (pin "6") (pinfunction "VDDIO_6") (pintype "power_in"))
      (node (ref "SENSOR2") (pin "8") (pinfunction "VDD_8") (pintype "power_in"))
      (node (ref "U2") (pin "17") (pinfunction "IO19_17") (pintype "bidirectional"))
    )
    (net (code "16") (name "INT_RTC") (class "Default")
      (node (ref "R1_PINH1") (pin "1") (pinfunction "1_1") (pintype "passive"))
      (node (ref "TP15") (pin "TP") (pinfunction "TP_TP") (pintype "input"))
      (node (ref "U2") (pin "8") (pinfunction "IO0_8") (pintype "bidirectional"))
      (node (ref "U3") (pin "3") (pinfunction "SQW/~{INT}_3") (pintype "output"))
    )
    (net (code "17") (name "IO{slash}BOOT") (class "Default")
      (node (ref "BOOT_BUTTON") (pin "3") (pinfunction "3_3") (pintype "passive"))
      (node (ref "BOOT_BUTTON") (pin "4") (pinfunction "4_4") (pintype "passive"))
      (node (ref "C6") (pin "1") (pinfunction "1_1") (pintype "passive"))
      (node (ref "R_BOOT") (pin "2") (pinfunction "2_2") (pintype "passive"))
      (node (ref "U2") (pin "15") (pinfunction "IO9_15") (pintype "bidirectional"))
    )
    (net (code "18") (name "IO{slash}CHANGE") (class "Default")
      (node (ref "C10") (pin "1") (pinfunction "1_1") (pintype "passive"))
      (node (ref "CHANGE_BUTTON") (pin "3") (pinfunction "3_3") (pintype "passive"))
      (node (ref "CHANGE_BUTTON") (pin "4") (pinfunction "4_4") (pintype "passive"))
      (node (ref "R_CHANGE") (pin "2") (pinfunction "2_2") (pintype "passive"))
      (node (ref "U2") (pin "23") (pinfunction "IO15_23") (pintype "bidirectional"))
    )
    (net (code "19") (name "MISO") (class "Default")
      (node (ref "D12") (pin "2") (pinfunction "2_2") (pintype "passive"))
      (node (ref "J4") (pin "P7") (pinfunction "DAT0_P7") (pintype "bidirectional"))
      (node (ref "R8") (pin "1") (pinfunction "1_1") (pintype "passive"))
      (node (ref "TP6") (pin "TP") (pinfunction "TP_TP") (pintype "input"))
      (node (ref "U1") (pin "2") (pinfunction "DO(IO1)_2") (pintype "bidirectional"))
      (node (ref "U2") (pin "27") (pinfunction "IO2_27") (pintype "bidirectional"))
    )
    (net (code "20") (name "MOSI") (class "Default")
      (node (ref "D11") (pin "2") (pinfunction "2_2") (pintype "passive"))
      (node (ref "J1") (pin "14") (pinfunction "14_14") (pintype "bidirectional"))
      (node (ref "J4") (pin "P3") (pinfunction "CMD_P3") (pintype "bidirectional"))
      (node (ref "R7") (pin "1") (pinfunction "1_1") (pintype "passive"))
      (node (ref "TP7") (pin "TP") (pinfunction "TP_TP") (pintype "input"))
      (node (ref "U1") (pin "5") (pinfunction "DI(IO0)_5") (pintype "bidirectional"))
      (node (ref "U2") (pin "7") (pinfunction "IO7_7") (pintype "bidirectional"))
    )
    (net (code "21") (name "Net-(CHG_LED-PadC)") (class "Default")
      (node (ref "CHG_LED") (pin "C") (pinfunction "C_C") (pintype "passive"))
      (node (ref "R1_BAT") (pin "2") (pinfunction "2_2") (pintype "passive"))
    )
    (net (code "22") (name "Net-(D2-CATHODE)") (class "Default")
      (node (ref "C1_BAT1") (pin "1") (pinfunction "1_1") (pintype "passive"))
      (node (ref "D2") (pin "1") (pinfunction "CATHODE_1") (pintype "bidirectional"))
      (node (ref "IC4") (pin "1") (pinfunction "VIN_1") (pintype "bidirectional"))
      (node (ref "IC4") (pin "3") (pinfunction "CE_3") (pintype "bidirectional"))
      (node (ref "Q1") (pin "2") (pinfunction "S_2") (pintype "bidirectional"))
    )
    (net (code "23") (name "Net-(D3-A)") (class "Default")
      (node (ref "C4") (pin "1") (pinfunction "1_1") (pintype "passive"))
      (node (ref "D3") (pin "2") (pinfunction "A_2") (pintype "bidirectional"))
      (node (ref "D4") (pin "1") (pinfunction "K_1") (pintype "bidirectional"))
    )
    (net (code "24") (name "Net-(D7-CATHODE)") (class "Default")
      (node (ref "D7") (pin "1") (pinfunction "CATHODE_1") (pintype "bidirectional"))
      (node (ref "R_CAPACITOR") (pin "2") (pinfunction "2_2") (pintype "passive"))
    )
    (net (code "25") (name "Net-(EPD_C1-Pad1)") (class "Default")
      (node (ref "EPD_C1") (pin "1") (pinfunction "1_1") (pintype "passive"))
      (node (ref "J1") (pin "4") (pinfunction "4_4") (pintype "bidirectional"))
    )
    (net (code "26") (name "Net-(EPD_C2-Pad1)") (class "Default")
      (node (ref "EPD_C2") (pin "1") (pinfunction "1_1") (pintype "passive"))
      (node (ref "J1") (pin "5") (pinfunction "5_5") (pintype "bidirectional"))
    )
    (net (code "27") (name "Net-(EPD_C6-Pad1)") (class "Default")
      (node (ref "EPD_C6") (pin "1") (pinfunction "1_1") (pintype "passive"))
      (node (ref "J1") (pin "18") (pinfunction "18_18") (pintype "bidirectional"))
    )
    (net (code "28") (name "Net-(EPD_C7-Pad1)") (class "Default")
      (node (ref "EPD_C7") (pin "1") (pinfunction "1_1") (pintype "passive"))
      (node (ref "J1") (pin "19") (pinfunction "19_19") (pintype "bidirectional"))
    )
    (net (code "29") (name "Net-(EPD_C8-Pad1)") (class "Default")
      (node (ref "EPD_C8") (pin "1") (pinfunction "1_1") (pintype "passive"))
      (node (ref "J1") (pin "20") (pinfunction "20_20") (pintype "bidirectional"))
    )
    (net (code "30") (name "Net-(EPD_C10-Pad1)") (class "Default")
      (node (ref "EPD_C10") (pin "1") (pinfunction "1_1") (pintype "passive"))
      (node (ref "J1") (pin "22") (pinfunction "22_22") (pintype "bidirectional"))
    )
    (net (code "31") (name "Net-(EPD_C12-Pad1)") (class "Default")
      (node (ref "EPD_C12") (pin "1") (pinfunction "1_1") (pintype "passive"))
      (node (ref "J1") (pin "24") (pinfunction "24_24") (pintype "bidirectional"))
    )
    (net (code "32") (name "Net-(IC1-CT)") (class "Default")
      (node (ref "C_DELAY") (pin "1") (pinfunction "1_1") (pintype "passive"))
      (node (ref "IC1") (pin "5") (pinfunction "CT_5") (pintype "bidirectional"))
    )
    (net (code "33") (name "Net-(J2-PadA5)") (class "Default")
      (node (ref "J2") (pin "A5") (pinfunction "A5_A5") (pintype "bidirectional"))
      (node (ref "R2-USB1") (pin "2") (pinfunction "2_2") (pintype "passive"))
    )
    (net (code "34") (name "Net-(J2-PadB5)") (class "Default")
      (node (ref "J2") (pin "B5") (pinfunction "B5_B5") (pintype "bidirectional"))
      (node (ref "R2-USB") (pin "1") (pinfunction "1_1") (pintype "passive"))
    )
    (net (code "35") (name "Net-(MCP73831-PROG)") (class "Default")
      (node (ref "MCP73831") (pin "5") (pinfunction "PROG_5") (pintype "input"))
      (node (ref "R2_BAT") (pin "2") (pinfunction "2_2") (pintype "passive"))
    )
    (net (code "36") (name "Net-(MCP73831-STAT)") (class "Default")
      (node (ref "MCP73831") (pin "1") (pinfunction "STAT_1") (pintype "output"))
      (node (ref "R1_BAT") (pin "1") (pinfunction "1_1") (pintype "passive"))
    )
    (net (code "37") (name "PREVGH") (class "Default")
      (node (ref "D5") (pin "1") (pinfunction "K_1") (pintype "bidirectional"))
      (node (ref "EPD_C9") (pin "1") (pinfunction "1_1") (pintype "passive"))
      (node (ref "J1") (pin "21") (pinfunction "21_21") (pintype "bidirectional"))
    )
    (net (code "38") (name "PREVGL") (class "Default")
      (node (ref "D4") (pin "2") (pinfunction "A_2") (pintype "bidirectional"))
      (node (ref "EPD_C11") (pin "1") (pinfunction "1_1") (pintype "passive"))
      (node (ref "J1") (pin "23") (pinfunction "23_23") (pintype "bidirectional"))
    )
    (net (code "39") (name "RESE") (class "Default")
      (node (ref "J1") (pin "3") (pinfunction "3_3") (pintype "bidirectional"))
      (node (ref "Q3") (pin "2") (pinfunction "S_2") (pintype "bidirectional"))
      (node (ref "R3") (pin "1") (pinfunction "1_1") (pintype "passive"))
    )
    (net (code "40") (name "RESE'") (class "Default")
      (node (ref "R2") (pin "2") (pinfunction "2_2") (pintype "passive"))
      (node (ref "R3") (pin "2") (pinfunction "2_2") (pintype "passive"))
      (node (ref "SJ1") (pin "2") (pinfunction "2_2") (pintype "passive"))
    )
    (net (code "41") (name "RESET") (class "Default")
      (node (ref "C5") (pin "1") (pinfunction "1_1") (pintype "passive"))
      (node (ref "IC1") (pin "1") (pinfunction "VOUT_1") (pintype "bidirectional"))
      (node (ref "RESET_BUTTON") (pin "3") (pinfunction "3_3") (pintype "passive"))
      (node (ref "RESET_BUTTON") (pin "4") (pinfunction "4_4") (pintype "passive"))
      (node (ref "R_RESET") (pin "2") (pinfunction "2_2") (pintype "passive"))
      (node (ref "U2") (pin "3") (pinfunction "EN_3") (pintype "input"))
    )
    (net (code "42") (name "RTC_RST") (class "Default")
      (node (ref "U2") (pin "16") (pinfunction "IO18_16") (pintype "bidirectional"))
      (node (ref "U3") (pin "4") (pinfunction "~{RST}_4") (pintype "input"))
    )
    (net (code "43") (name "RX") (class "Default")
      (node (ref "TP2") (pin "TP") (pinfunction "TP_TP") (pintype "input"))
      (node (ref "U2") (pin "24") (pinfunction "RXD0/GPIO17_24") (pintype "bidirectional"))
    )
    (net (code "44") (name "SCK") (class "Default")
      (node (ref "D10") (pin "2") (pinfunction "2_2") (pintype "passive"))
      (node (ref "J1") (pin "13") (pinfunction "13_13") (pintype "bidirectional"))
      (node (ref "J4") (pin "P5") (pinfunction "CLK_P5") (pintype "bidirectional"))
      (node (ref "R6") (pin "1") (pinfunction "1_1") (pintype "passive"))
      (node (ref "TP8") (pin "TP") (pinfunction "TP_TP") (pintype "input"))
      (node (ref "U1") (pin "6") (pinfunction "CLK_6") (pintype "input"))
      (node (ref "U2") (pin "6") (pinfunction "IO6_6") (pintype "bidirectional"))
    )
    (net (code "45") (name "SCL") (class "Default")
      (node (ref "J3") (pin "4") (pinfunction "4_4") (pintype "passive"))
      (node (ref "R2_PINH") (pin "1") (pinfunction "1_1") (pintype "passive"))
      (node (ref "SENSOR2") (pin "4") (pinfunction "SCK_4") (pintype "input"))
      (node (ref "U2") (pin "20") (pinfunction "IO22_20") (pintype "bidirectional"))
      (node (ref "U3") (pin "16") (pinfunction "SCL_16") (pintype "input"))
      (node (ref "U4") (pin "7") (pinfunction "SCL_7") (pintype "input"))
    )
    (net (code "46") (name "SDA") (class "Default")
      (node (ref "J3") (pin "3") (pinfunction "3_3") (pintype "passive"))
      (node (ref "R1_PINH") (pin "1") (pinfunction "1_1") (pintype "passive"))
      (node (ref "SENSOR2") (pin "3") (pinfunction "SDI_3") (pintype "bidirectional"))
      (node (ref "U2") (pin "19") (pinfunction "IO21_19") (pintype "bidirectional"))
      (node (ref "U3") (pin "15") (pinfunction "SDA_15") (pintype "bidirectional"))
      (node (ref "U4") (pin "8") (pinfunction "SDA_8") (pintype "bidirectional"))
    )
    (net (code "47") (name "SRC") (class "Default")
      (node (ref "C4") (pin "2") (pinfunction "2_2") (pintype "passive"))
      (node (ref "D5") (pin "2") (pinfunction "A_2") (pintype "bidirectional"))
      (node (ref "L1") (pin "1") (pinfunction "1_1") (pintype "passive"))
      (node (ref "Q3") (pin "3") (pinfunction "D_3") (pintype "bidirectional"))
    )
    (net (code "48") (name "SS_SD") (class "Default")
      (node (ref "D8") (pin "2") (pinfunction "2_2") (pintype "passive"))
      (node (ref "J4") (pin "P2") (pinfunction "CD/DAT3_P2") (pintype "bidirectional"))
      (node (ref "R10") (pin "1") (pinfunction "1_1") (pintype "passive"))
      (node (ref "U2") (pin "4") (pinfunction "IO4_4") (pintype "bidirectional"))
    )
    (net (code "49") (name "TX") (class "Default")
      (node (ref "TP1") (pin "TP") (pinfunction "TP_TP") (pintype "input"))
      (node (ref "U2") (pin "25") (pinfunction "TXD0/GPIO16_25") (pintype "bidirectional"))
    )
    (net (code "50") (name "USB_D+") (class "Default")
      (node (ref "D1") (pin "1") (pinfunction "I/O1_1_1") (pintype "bidirectional"))
      (node (ref "U2") (pin "14") (pinfunction "IO13_14") (pintype "bidirectional"))
    )
    (net (code "51") (name "USB_D-") (class "Default")
      (node (ref "D1") (pin "3") (pinfunction "I/O2_1_3") (pintype "bidirectional"))
      (node (ref "U2") (pin "13") (pinfunction "IO12_13") (pintype "bidirectional"))
    )
    (net (code "52") (name "VBAT") (class "Default")
      (node (ref "C2_BAT") (pin "1") (pinfunction "1_1") (pintype "passive"))
      (node (ref "MCP73831") (pin "3") (pinfunction "VBAT_3") (pintype "power_in"))
      (node (ref "Q1") (pin "3") (pinfunction "D_3") (pintype "bidirectional"))
      (node (ref "TP3") (pin "TP") (pinfunction "TP_TP") (pintype "input"))
      (node (ref "U4") (pin "2") (pinfunction "CELL_2") (pintype "power_in"))
      (node (ref "U4") (pin "3") (pinfunction "VDD_3") (pintype "power_in"))
    )
    (net (code "53") (name "VBUS") (class "Default")
      (node (ref "C1_BAT") (pin "1") (pinfunction "1_1") (pintype "passive"))
      (node (ref "C4_USB") (pin "1") (pinfunction "1_1") (pintype "passive"))
      (node (ref "C5_USB") (pin "1") (pinfunction "1_1") (pintype "passive"))
      (node (ref "CHG_LED") (pin "A") (pinfunction "A_A") (pintype "passive"))
      (node (ref "D1") (pin "5") (pinfunction "VBUS_5") (pintype "bidirectional"))
      (node (ref "D2") (pin "2") (pinfunction "ANODE_2") (pintype "bidirectional"))
      (node (ref "MCP73831") (pin "4") (pinfunction "VIN_4") (pintype "power_in"))
      (node (ref "PFMF.050.1") (pin "2") (pinfunction "2_2") (pintype "passive"))
      (node (ref "Q1") (pin "1") (pinfunction "G_1") (pintype "bidirectional"))
      (node (ref "R1_PWRUSB") (pin "2") (pinfunction "2_2") (pintype "passive"))
      (node (ref "TP14") (pin "TP") (pinfunction "TP_TP") (pintype "input"))
    )
    (net (code "54") (name "VRTC") (class "Default")
      (node (ref "C10_SUPERCAP") (pin "2") (pinfunction "2_2") (pintype "passive"))
      (node (ref "C8") (pin "1") (pinfunction "1_1") (pintype "passive"))
      (node (ref "R_CAPACITOR") (pin "1") (pinfunction "1_1") (pintype "passive"))
      (node (ref "U3") (pin "14") (pinfunction "VBAT_14") (pintype "power_in"))
    )
    (net (code "55") (name "VUSB") (class "Default")
      (node (ref "J2") (pin "A4") (pinfunction "A4_A4") (pintype "bidirectional"))
      (node (ref "J2") (pin "A9") (pinfunction "A9_A9") (pintype "bidirectional"))
      (node (ref "J2") (pin "B4") (pinfunction "B4_B4") (pintype "bidirectional"))
      (node (ref "J2") (pin "B9") (pinfunction "B9_B9") (pintype "bidirectional"))
      (node (ref "PFMF.050.1") (pin "1") (pinfunction "1_1") (pintype "passive"))
    )
    (net (code "56") (name "unconnected-(IC1-NC-Pad4)") (class "Default")
      (node (ref "IC1") (pin "4") (pinfunction "NC_4") (pintype "no_connect"))
    )
    (net (code "57") (name "unconnected-(IC4-NC-Pad4)") (class "Default")
      (node (ref "IC4") (pin "4") (pinfunction "NC_4") (pintype "no_connect"))
    )
    (net (code "58") (name "unconnected-(J1-Pad1)") (class "Default")
      (node (ref "J1") (pin "1") (pinfunction "1_1") (pintype "bidirectional"))
    )
    (net (code "59") (name "unconnected-(J1-Pad6)") (class "Default")
      (node (ref "J1") (pin "6") (pinfunction "6_6") (pintype "bidirectional"))
    )
    (net (code "60") (name "unconnected-(J1-Pad7)") (class "Default")
      (node (ref "J1") (pin "7") (pinfunction "7_7") (pintype "bidirectional"))
    )
    (net (code "61") (name "unconnected-(J2-PadA8)") (class "Default")
      (node (ref "J2") (pin "A8") (pinfunction "A8_A8") (pintype "bidirectional"))
    )
    (net (code "62") (name "unconnected-(J2-PadB8)") (class "Default")
      (node (ref "J2") (pin "B8") (pinfunction "B8_B8") (pintype "bidirectional"))
    )
    (net (code "63") (name "unconnected-(J4-DAT1-PadP8)") (class "Default")
      (node (ref "J4") (pin "P8") (pinfunction "DAT1_P8") (pintype "bidirectional"))
    )
    (net (code "64") (name "unconnected-(J4-DAT2-PadP1)") (class "Default")
      (node (ref "J4") (pin "P1") (pinfunction "DAT2_P1") (pintype "bidirectional"))
    )
    (net (code "65") (name "unconnected-(J4-DETECTION_1-PadS1)") (class "Default")
      (node (ref "J4") (pin "S1") (pinfunction "DETECTION_1_S1") (pintype "bidirectional"))
    )
    (net (code "66") (name "unconnected-(J4-DETECTION_2-PadS2)") (class "Default")
      (node (ref "J4") (pin "S2") (pinfunction "DETECTION_2_S2") (pintype "bidirectional"))
    )
    (net (code "67") (name "unconnected-(U2-NC-Pad22)") (class "Default")
      (node (ref "U2") (pin "22") (pinfunction "NC_22") (pintype "no_connect"))
    )
    (net (code "68") (name "unconnected-(U4-~{ALERT}-Pad5)") (class "Default")
      (node (ref "U4") (pin "5") (pinfunction "~{ALERT}_5") (pintype "output"))
    )
  )
)
